# main_sheet.net
KiCad netlist of a schematic drawn in Altium Designer
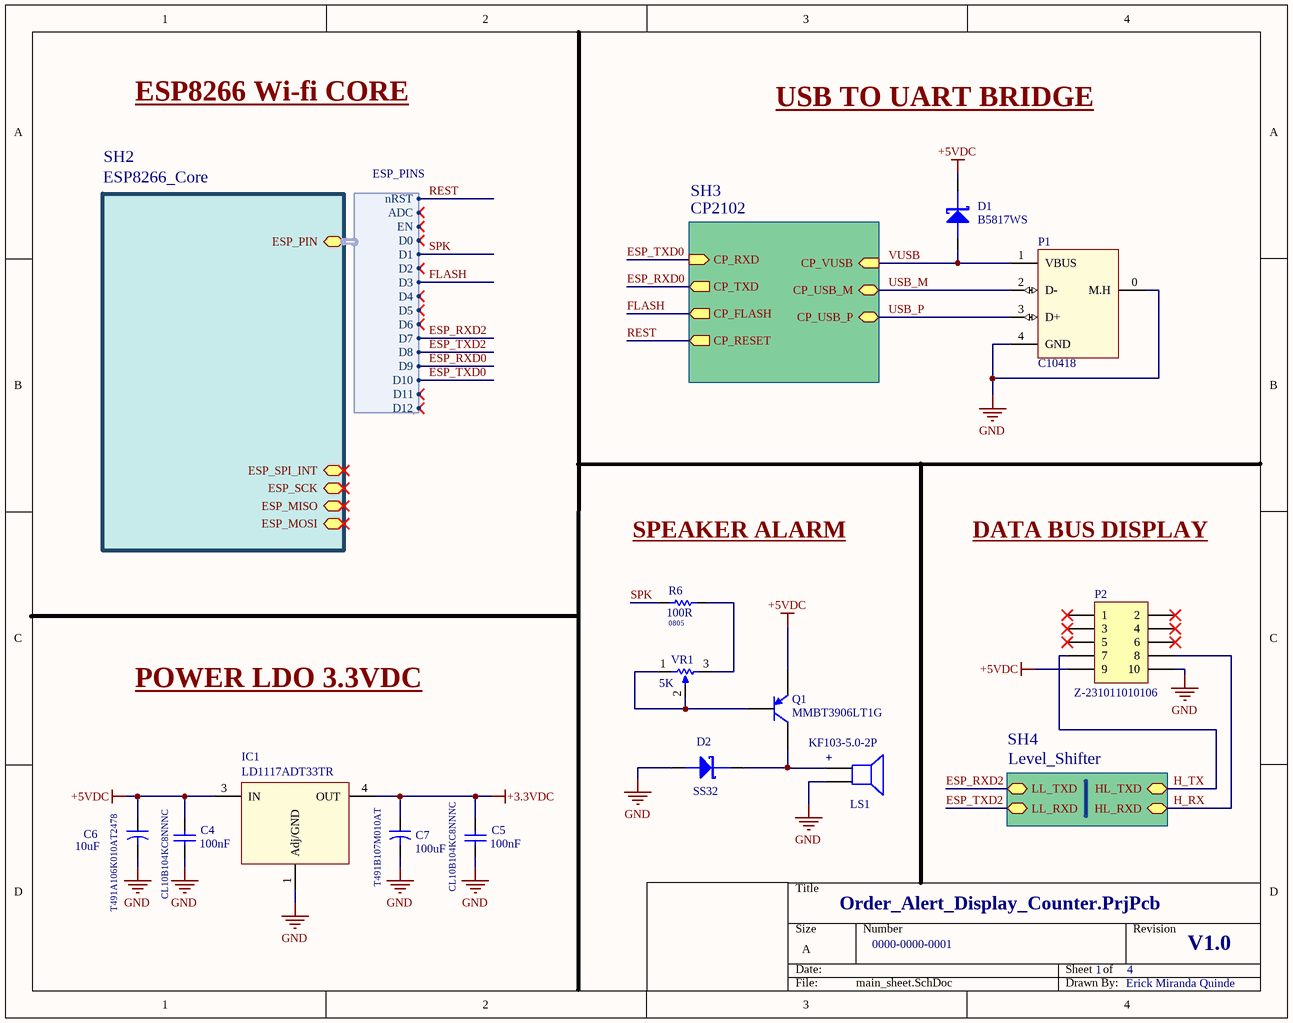
[diagram p0: main_sheet.SchDoc]

(export (version "E")
  (design (tool "Eeschema 10.0.6"))
  (components
    (comp (ref "C4")
      (value "CL10B104KC8NNNC")
      (footprint "C0603C104K5RACTU")
      (fields (field (name "ALTIUM_VALUE") "100nF") (field (name "LCSC PART") "C15725"))
      (libsource (lib "IDETEC LIB") (part "Cap 100nF (0603)"))
    )
    (comp (ref "C5")
      (value "CL10B104KC8NNNC")
      (footprint "C0603C104K5RACTU")
      (fields (field (name "ALTIUM_VALUE") "100nF") (field (name "LCSC PART") "C15725"))
      (libsource (lib "IDETEC LIB") (part "Cap 100nF (0603)"))
    )
    (comp (ref "C6")
      (value "T491A106K010AT2478")
      (footprint "3216 Case-A")
      (description "CAP TANT 10UF 6.3V 20% 1206")
      (fields (field (name "ALTIUM_VALUE") "10uF") (field (name "LCSC PART") "C110052"))
      (libsource (lib "IDETEC LIB") (part "T491A106M006AT"))
    )
    (comp (ref "C7")
      (value "T491B107M010AT")
      (footprint "TAJB107M006RNJ")
      (description "Capacitor")
      (fields (field (name "ALTIUM_VALUE") "100uF") (field (name "LCSC PART") "C90975"))
      (libsource (lib "IDETEC LIB") (part "Cap 10uF (C3216)"))
    )
    (comp (ref "D1")
      (value "B5817WS")
      (footprint "Diode S4")
      (fields (field (name "LCSC PART") "C122854"))
      (libsource (lib "IDETEC LIB") (part "1N5817"))
    )
    (comp (ref "D2")
      (value "SS32")
      (footprint "DO-214AC)")
      (description "DIODE SCHOTTKY 40V 3A SMA")
      (fields (field (name "LCSC PART") "C34897"))
      (libsource (lib "IDETEC LIB") (part "CD214A-B340LF"))
    )
    (comp (ref "IC1")
      (value "LD1117ADT33TR")
      (footprint "TO252")
      (description "800mA Low-Dropout Linear Regulator")
      (fields (field (name "MANUFACTURER") "National Semiconductor") (field (name "LCSC PART") "C157401"))
      (libsource (lib "TSK Library") (part "LM1117DT"))
    )
    (comp (ref "LS1")
      (value "KF103-5.0-2P")
      (footprint "VERDE 2pin")
      (description "Speaker")
      (fields (field (name "LCSC PART") "C475088") (field (name "PUBLISHER") "Altium Limited"))
      (libsource (lib "IDETEC LIB") (part "Speaker"))
    )
    (comp (ref "P1")
      (value "C10418")
      (footprint "USB_MICRO_B_AT")
      (description "USB Micro")
      (libsource (lib "IDETEC LIB") (part "USB Mini"))
    )
    (comp (ref "P2")
      (value "Z-231011010106")
      (footprint "IDC5X2")
      (description "Header, 5-Pin, Dual row")
      (fields (field (name "LCSC PART") "C221045") (field (name "PUBLISHER") "Altium Limited"))
      (libsource (lib "IDETEC LIB") (part "IDC  5X2"))
    )
    (comp (ref "Q1")
      (value "MMBT3906LT1G")
      (footprint "SOT-23-TT3_N")
      (fields
        (field (name "MANUFACTURER") "Micro Commercial Co")
        (field (name "MANUFACTURER PART NUMBER") "2N3906-AP")
        (field (name "LCSC PART") "C53444")
      )
      (libsource (lib "IDETEC LIB") (part "2N3906"))
    )
    (comp (ref "R6")
      (value "100R")
      (footprint "RES-0805")
      (description "Resistor")
      (fields
        (field (name "PACKAGE") "0805")
        (field (name "LCSC PART") "C44786")
        (field (name "Comment") "TC0525D1000T5E")
        (field (name "PUBLISHER") "Altium Limited")
      )
      (libsource (lib "IDETEC LIB") (part "Resistor"))
    )
    (comp (ref "VR1")
      (value "5K")
      (footprint "POT LIN VR1")
      (description "Trimmer Cermet 104")
      (fields (field (name "PARTNUM") "3362P-1-502LF") (field (name "LCSC PART") "C81260"))
      (libsource (lib "IDETEC LIB") (part "Trimmer Cermet 104"))
    )
  )
  (nets
    (net (code "2") (name "+3.3VDC") (class "Default")
      (node (ref "C5") (pin "2") (pinfunction "2_2") (pintype "passive"))
      (node (ref "C7") (pin "1") (pinfunction "1_1") (pintype "passive"))
      (node (ref "IC1") (pin "4") (pinfunction "OUT_4") (pintype "passive"))
    )
    (net (code "3") (name "+5VDC") (class "Default")
      (node (ref "C4") (pin "2") (pinfunction "2_2") (pintype "passive"))
      (node (ref "C6") (pin "1") (pinfunction "1_1") (pintype "passive"))
      (node (ref "D1") (pin "1") (pinfunction "K_1") (pintype "passive"))
      (node (ref "IC1") (pin "3") (pinfunction "IN_3") (pintype "passive"))
      (node (ref "P2") (pin "9") (pinfunction "9_9") (pintype "passive"))
      (node (ref "Q1") (pin "2") (pinfunction "E_2") (pintype "passive"))
    )
    (net (code "13") (name "/H_RX") (class "Default")
      (node (ref "P2") (pin "8") (pinfunction "8_8") (pintype "passive"))
    )
    (net (code "14") (name "/H_TX") (class "Default")
      (node (ref "P2") (pin "7") (pinfunction "7_7") (pintype "passive"))
    )
    (net (code "16") (name "/SPK") (class "Default")
      (node (ref "R6") (pin "1") (pinfunction "1_1") (pintype "passive"))
    )
    (net (code "17") (name "/USB_M") (class "Default")
      (node (ref "P1") (pin "2") (pinfunction "D-_2") (pintype "bidirectional"))
    )
    (net (code "18") (name "/USB_P") (class "Default")
      (node (ref "P1") (pin "3") (pinfunction "D+_3") (pintype "bidirectional"))
    )
    (net (code "19") (name "/VUSB") (class "Default")
      (node (ref "D1") (pin "2") (pinfunction "A_2") (pintype "passive"))
      (node (ref "P1") (pin "1") (pinfunction "VBUS_1") (pintype "power_in"))
    )
    (net (code "21") (name "GND") (class "Default")
      (node (ref "C4") (pin "1") (pinfunction "1_1") (pintype "passive"))
      (node (ref "C5") (pin "1") (pinfunction "1_1") (pintype "passive"))
      (node (ref "C6") (pin "2") (pinfunction "2_2") (pintype "passive"))
      (node (ref "C7") (pin "2") (pinfunction "2_2") (pintype "passive"))
      (node (ref "D2") (pin "2") (pinfunction "A_2") (pintype "passive"))
      (node (ref "IC1") (pin "1") (pinfunction "Adj/GND_1") (pintype "passive"))
      (node (ref "LS1") (pin "2") (pinfunction "2_2") (pintype "passive"))
      (node (ref "P1") (pin "0") (pinfunction "M.H_0") (pintype "passive"))
      (node (ref "P1") (pin "4") (pinfunction "GND_4") (pintype "passive"))
      (node (ref "P2") (pin "10") (pinfunction "10_10") (pintype "passive"))
    )
    (net (code "22") (name "Net-(D2-K)") (class "Default")
      (node (ref "D2") (pin "1") (pinfunction "K_1") (pintype "passive"))
      (node (ref "LS1") (pin "1") (pinfunction "1_1") (pintype "passive"))
      (node (ref "Q1") (pin "3") (pinfunction "C_3") (pintype "passive"))
    )
    (net (code "23") (name "Net-(Q1-B)") (class "Default")
      (node (ref "Q1") (pin "1") (pinfunction "B_1") (pintype "passive"))
      (node (ref "VR1") (pin "1") (pinfunction "1_1") (pintype "passive"))
      (node (ref "VR1") (pin "2") (pinfunction "2_2") (pintype "passive"))
    )
    (net (code "24") (name "Net-(R6-Pad2)") (class "Default")
      (node (ref "R6") (pin "2") (pinfunction "2_2") (pintype "passive"))
      (node (ref "VR1") (pin "3") (pinfunction "3_3") (pintype "passive"))
    )
    (net (code "25") (name "unconnected-(P2-Pad1)") (class "Default")
      (node (ref "P2") (pin "1") (pinfunction "1_1") (pintype "passive+no_connect"))
    )
    (net (code "26") (name "unconnected-(P2-Pad2)") (class "Default")
      (node (ref "P2") (pin "2") (pinfunction "2_2") (pintype "passive+no_connect"))
    )
    (net (code "27") (name "unconnected-(P2-Pad3)") (class "Default")
      (node (ref "P2") (pin "3") (pinfunction "3_3") (pintype "passive+no_connect"))
    )
    (net (code "28") (name "unconnected-(P2-Pad4)") (class "Default")
      (node (ref "P2") (pin "4") (pinfunction "4_4") (pintype "passive+no_connect"))
    )
    (net (code "29") (name "unconnected-(P2-Pad5)") (class "Default")
      (node (ref "P2") (pin "5") (pinfunction "5_5") (pintype "passive+no_connect"))
    )
    (net (code "30") (name "unconnected-(P2-Pad6)") (class "Default")
      (node (ref "P2") (pin "6") (pinfunction "6_6") (pintype "passive+no_connect"))
    )
  )
)
